# main.net
KiCad netlist of a schematic drawn in EAGLE
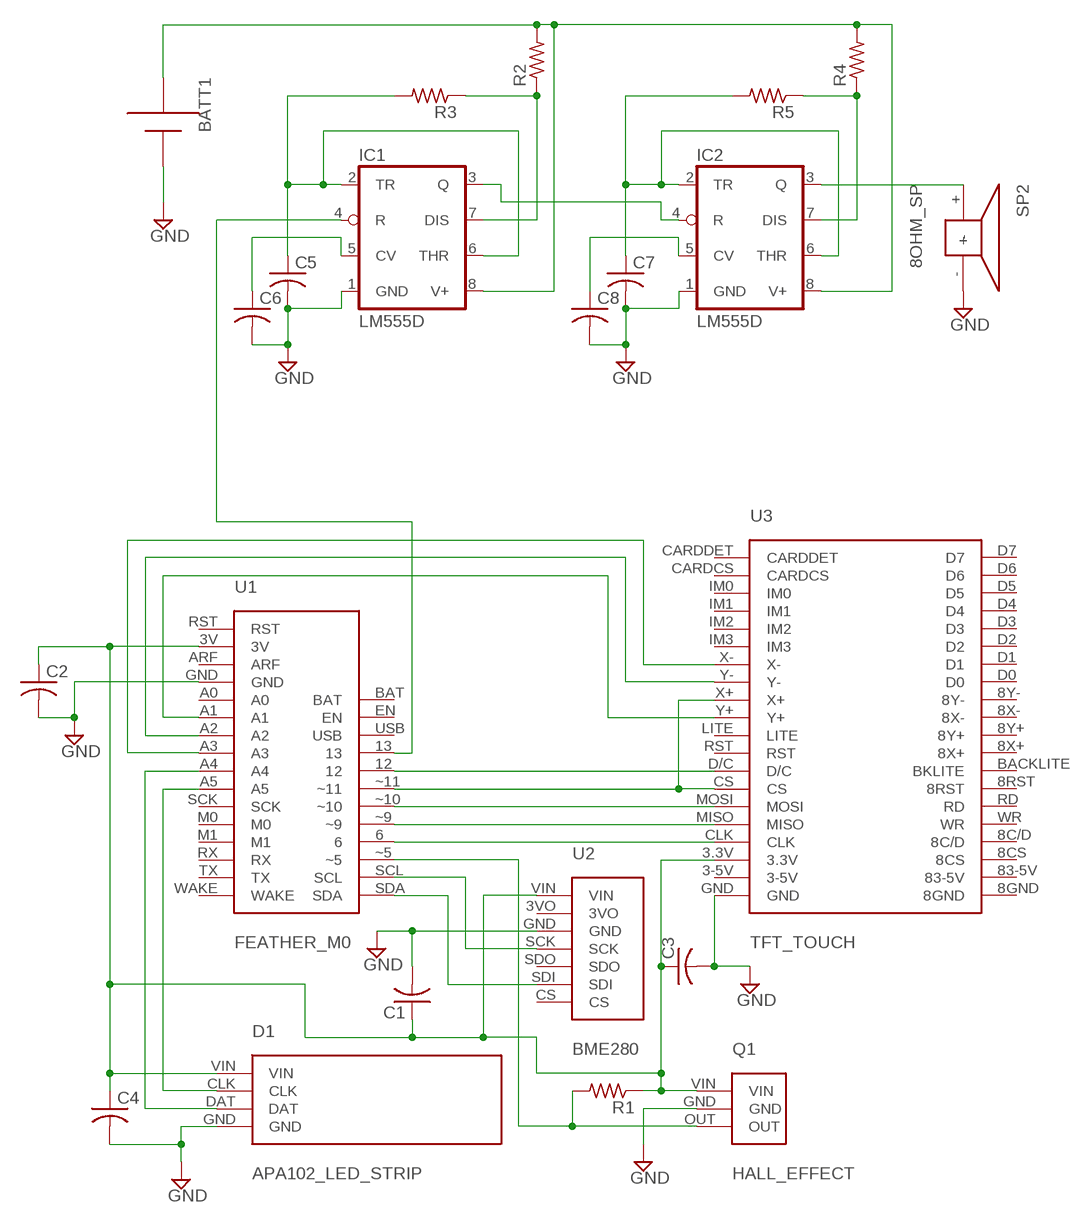
[diagram p0: schematic, sheet 1]

(export (version "E")
  (design (tool "Eeschema 10.0.6"))
  (components
    (comp (ref "BATT1")
      (value "AAA")
      (footprint "eagle-import:12BH412")
      (libsource (lib "eagle-import") (part "AAA"))
    )
    (comp (ref "C1")
      (value "C-US025-024X044")
      (footprint "eagle-import:C025-024X044")
      (libsource (lib "eagle-import") (part "C-US025-024X044"))
    )
    (comp (ref "C2")
      (value "C-US025-024X044")
      (footprint "eagle-import:C025-024X044")
      (libsource (lib "eagle-import") (part "C-US025-024X044"))
    )
    (comp (ref "C3")
      (value "C-US025-024X044")
      (footprint "eagle-import:C025-024X044")
      (libsource (lib "eagle-import") (part "C-US025-024X044"))
    )
    (comp (ref "C4")
      (value "C-US025-024X044")
      (footprint "eagle-import:C025-024X044")
      (libsource (lib "eagle-import") (part "C-US025-024X044"))
    )
    (comp (ref "C5")
      (value "C-US025-024X044")
      (footprint "eagle-import:C025-024X044")
      (libsource (lib "eagle-import") (part "C-US025-024X044"))
    )
    (comp (ref "C6")
      (value "C-US025-024X044")
      (footprint "eagle-import:C025-024X044")
      (libsource (lib "eagle-import") (part "C-US025-024X044"))
    )
    (comp (ref "C7")
      (value "C-US025-024X044")
      (footprint "eagle-import:C025-024X044")
      (libsource (lib "eagle-import") (part "C-US025-024X044"))
    )
    (comp (ref "C8")
      (value "C-US025-024X044")
      (footprint "eagle-import:C025-024X044")
      (libsource (lib "eagle-import") (part "C-US025-024X044"))
    )
    (comp (ref "D1")
      (value "APA102_LED_STRIP")
      (footprint "eagle-import:APA102_LED_STRIP")
      (libsource (lib "eagle-import") (part "APA102_LED_STRIP"))
    )
    (comp (ref "IC1")
      (value "LM555D")
      (footprint "eagle-import:SO08")
      (libsource (lib "eagle-import") (part "555DLM"))
    )
    (comp (ref "IC2")
      (value "LM555D")
      (footprint "eagle-import:SO08")
      (libsource (lib "eagle-import") (part "555DLM"))
    )
    (comp (ref "Q1")
      (value "HALL_EFFECT")
      (footprint "eagle-import:HALL_EFFECT")
      (libsource (lib "eagle-import") (part "HALL_EFFECT"))
    )
    (comp (ref "R1")
      (value "R-US_0207/5V")
      (footprint "eagle-import:0207_5V")
      (libsource (lib "eagle-import") (part "R-US_0207/5V"))
    )
    (comp (ref "R2")
      (value "R-US_0207/5V")
      (footprint "eagle-import:0207_5V")
      (libsource (lib "eagle-import") (part "R-US_0207/5V"))
    )
    (comp (ref "R3")
      (value "R-US_0207/5V")
      (footprint "eagle-import:0207_5V")
      (libsource (lib "eagle-import") (part "R-US_0207/5V"))
    )
    (comp (ref "R4")
      (value "R-US_0207/5V")
      (footprint "eagle-import:0207_5V")
      (libsource (lib "eagle-import") (part "R-US_0207/5V"))
    )
    (comp (ref "R5")
      (value "R-US_0207/5V")
      (footprint "eagle-import:0207_5V")
      (libsource (lib "eagle-import") (part "R-US_0207/5V"))
    )
    (comp (ref "SP2")
      (value "8OHM_SP")
      (footprint "eagle-import:8OHM_SP")
      (libsource (lib "eagle-import") (part "8OHM_SP"))
    )
    (comp (ref "U1")
      (value "FEATHER_M0")
      (footprint "eagle-import:FEATHER_M0")
      (libsource (lib "eagle-import") (part "FEATHER_M0"))
    )
    (comp (ref "U2")
      (value "BME280")
      (footprint "eagle-import:BME280")
      (libsource (lib "eagle-import") (part "BME280"))
    )
    (comp (ref "U3")
      (value "TFT_TOUCH")
      (footprint "eagle-import:TFT_TOUCH")
      (libsource (lib "eagle-import") (part "TFT_TOUCH"))
    )
  )
  (nets
    (net (code "1") (name "GND") (class "Default")
      (node (ref "BATT1") (pin "+") (pinfunction "+_+") (pintype "bidirectional"))
      (node (ref "C1") (pin "2") (pinfunction "2_2") (pintype "passive"))
      (node (ref "C2") (pin "2") (pinfunction "2_2") (pintype "passive"))
      (node (ref "C3") (pin "2") (pinfunction "2_2") (pintype "passive"))
      (node (ref "C4") (pin "2") (pinfunction "2_2") (pintype "passive"))
      (node (ref "C5") (pin "2") (pinfunction "2_2") (pintype "passive"))
      (node (ref "C6") (pin "2") (pinfunction "2_2") (pintype "passive"))
      (node (ref "C7") (pin "2") (pinfunction "2_2") (pintype "passive"))
      (node (ref "C8") (pin "2") (pinfunction "2_2") (pintype "passive"))
      (node (ref "D1") (pin "GND") (pinfunction "GND_GND") (pintype "bidirectional"))
      (node (ref "IC1") (pin "1") (pinfunction "GND_1") (pintype "power_in"))
      (node (ref "IC2") (pin "1") (pinfunction "GND_1") (pintype "power_in"))
      (node (ref "Q1") (pin "GND") (pinfunction "GND_GND") (pintype "bidirectional"))
      (node (ref "SP2") (pin "-") (pinfunction "-_-") (pintype "bidirectional"))
      (node (ref "U1") (pin "GND") (pinfunction "GND_GND") (pintype "bidirectional"))
      (node (ref "U2") (pin "GND") (pinfunction "GND_GND") (pintype "bidirectional"))
      (node (ref "U3") (pin "GND") (pinfunction "GND_GND") (pintype "bidirectional"))
    )
    (net (code "2") (name "Net-(C1-Pad1)") (class "Default")
      (node (ref "C1") (pin "1") (pinfunction "1_1") (pintype "passive"))
      (node (ref "C2") (pin "1") (pinfunction "1_1") (pintype "passive"))
      (node (ref "C3") (pin "1") (pinfunction "1_1") (pintype "passive"))
      (node (ref "C4") (pin "1") (pinfunction "1_1") (pintype "passive"))
      (node (ref "D1") (pin "VIN") (pinfunction "VIN_VIN") (pintype "bidirectional"))
      (node (ref "Q1") (pin "VIN") (pinfunction "VIN_VIN") (pintype "bidirectional"))
      (node (ref "R1") (pin "1") (pinfunction "1_1") (pintype "passive"))
      (node (ref "U1") (pin "3V") (pinfunction "3V_3V") (pintype "bidirectional"))
      (node (ref "U2") (pin "VIN") (pinfunction "VIN_VIN") (pintype "bidirectional"))
      (node (ref "U3") (pin "3.3V") (pinfunction "3.3V_3.3V") (pintype "bidirectional"))
    )
    (net (code "3") (name "Net-(D1-PadCLK)") (class "Default")
      (node (ref "D1") (pin "CLK") (pinfunction "CLK_CLK") (pintype "bidirectional"))
      (node (ref "U1") (pin "A5") (pinfunction "A5_A5") (pintype "bidirectional"))
    )
    (net (code "4") (name "Net-(D1-PadDAT)") (class "Default")
      (node (ref "D1") (pin "DAT") (pinfunction "DAT_DAT") (pintype "bidirectional"))
      (node (ref "U1") (pin "A4") (pinfunction "A4_A4") (pintype "bidirectional"))
    )
    (net (code "5") (name "Net-(IC1-CV)") (class "Default")
      (node (ref "C6") (pin "1") (pinfunction "1_1") (pintype "passive"))
      (node (ref "IC1") (pin "5") (pinfunction "CV_5") (pintype "input"))
    )
    (net (code "6") (name "Net-(IC1-DIS)") (class "Default")
      (node (ref "IC1") (pin "7") (pinfunction "DIS_7") (pintype "input"))
      (node (ref "R2") (pin "1") (pinfunction "1_1") (pintype "passive"))
      (node (ref "R3") (pin "1") (pinfunction "1_1") (pintype "passive"))
    )
    (net (code "7") (name "Net-(IC1-Q)") (class "Default")
      (node (ref "IC1") (pin "3") (pinfunction "Q_3") (pintype "output"))
      (node (ref "IC2") (pin "4") (pinfunction "R_4") (pintype "input"))
    )
    (net (code "8") (name "Net-(IC1-R)") (class "Default")
      (node (ref "IC1") (pin "4") (pinfunction "R_4") (pintype "input"))
      (node (ref "U1") (pin "13") (pinfunction "13_13") (pintype "bidirectional"))
    )
    (net (code "9") (name "Net-(IC1-THR)") (class "Default")
      (node (ref "C5") (pin "1") (pinfunction "1_1") (pintype "passive"))
      (node (ref "IC1") (pin "2") (pinfunction "TR_2") (pintype "input"))
      (node (ref "IC1") (pin "6") (pinfunction "THR_6") (pintype "input"))
      (node (ref "R3") (pin "2") (pinfunction "2_2") (pintype "passive"))
    )
    (net (code "10") (name "Net-(IC1-V+)") (class "Default")
      (node (ref "BATT1") (pin "-") (pinfunction "-_-") (pintype "bidirectional"))
      (node (ref "IC1") (pin "8") (pinfunction "V+_8") (pintype "power_in"))
      (node (ref "IC2") (pin "8") (pinfunction "V+_8") (pintype "power_in"))
      (node (ref "R2") (pin "2") (pinfunction "2_2") (pintype "passive"))
      (node (ref "R4") (pin "2") (pinfunction "2_2") (pintype "passive"))
    )
    (net (code "11") (name "Net-(IC2-CV)") (class "Default")
      (node (ref "C8") (pin "1") (pinfunction "1_1") (pintype "passive"))
      (node (ref "IC2") (pin "5") (pinfunction "CV_5") (pintype "input"))
    )
    (net (code "12") (name "Net-(IC2-DIS)") (class "Default")
      (node (ref "IC2") (pin "7") (pinfunction "DIS_7") (pintype "input"))
      (node (ref "R4") (pin "1") (pinfunction "1_1") (pintype "passive"))
      (node (ref "R5") (pin "1") (pinfunction "1_1") (pintype "passive"))
    )
    (net (code "13") (name "Net-(IC2-Q)") (class "Default")
      (node (ref "IC2") (pin "3") (pinfunction "Q_3") (pintype "output"))
      (node (ref "SP2") (pin "+") (pinfunction "+_+") (pintype "bidirectional"))
    )
    (net (code "14") (name "Net-(IC2-THR)") (class "Default")
      (node (ref "C7") (pin "1") (pinfunction "1_1") (pintype "passive"))
      (node (ref "IC2") (pin "2") (pinfunction "TR_2") (pintype "input"))
      (node (ref "IC2") (pin "6") (pinfunction "THR_6") (pintype "input"))
      (node (ref "R5") (pin "2") (pinfunction "2_2") (pintype "passive"))
    )
    (net (code "15") (name "Net-(U1-Pad6)") (class "Default")
      (node (ref "U1") (pin "6") (pinfunction "6_6") (pintype "bidirectional"))
      (node (ref "U3") (pin "CLK") (pinfunction "CLK_CLK") (pintype "bidirectional"))
    )
    (net (code "16") (name "Net-(U1-Pad12)") (class "Default")
      (node (ref "U1") (pin "12") (pinfunction "12_12") (pintype "bidirectional"))
      (node (ref "U3") (pin "D/C") (pinfunction "D/C_D/C") (pintype "bidirectional"))
    )
    (net (code "17") (name "Net-(U1-PadA1)") (class "Default")
      (node (ref "U1") (pin "A1") (pinfunction "A1_A1") (pintype "bidirectional"))
      (node (ref "U3") (pin "Y+") (pinfunction "Y+_Y+") (pintype "bidirectional"))
    )
    (net (code "18") (name "Net-(U1-PadA2)") (class "Default")
      (node (ref "U1") (pin "A2") (pinfunction "A2_A2") (pintype "bidirectional"))
      (node (ref "U3") (pin "Y-") (pinfunction "Y-_Y-") (pintype "bidirectional"))
    )
    (net (code "19") (name "Net-(U1-PadA3)") (class "Default")
      (node (ref "U1") (pin "A3") (pinfunction "A3_A3") (pintype "bidirectional"))
      (node (ref "U3") (pin "X-") (pinfunction "X-_X-") (pintype "bidirectional"))
    )
    (net (code "20") (name "Net-(U1-PadSCL)") (class "Default")
      (node (ref "U1") (pin "SCL") (pinfunction "SCL_SCL") (pintype "bidirectional"))
      (node (ref "U2") (pin "SCK") (pinfunction "SCK_SCK") (pintype "bidirectional"))
    )
    (net (code "21") (name "Net-(U1-PadSDA)") (class "Default")
      (node (ref "U1") (pin "SDA") (pinfunction "SDA_SDA") (pintype "bidirectional"))
      (node (ref "U2") (pin "SDI") (pinfunction "SDI_SDI") (pintype "bidirectional"))
    )
    (net (code "22") (name "Net-(U1-~{5})") (class "Default")
      (node (ref "Q1") (pin "OUT") (pinfunction "OUT_OUT") (pintype "bidirectional"))
      (node (ref "R1") (pin "2") (pinfunction "2_2") (pintype "passive"))
      (node (ref "U1") (pin "~5") (pinfunction "~{5}_~5") (pintype "bidirectional"))
    )
    (net (code "23") (name "Net-(U1-~{9})") (class "Default")
      (node (ref "U1") (pin "~9") (pinfunction "~{9}_~9") (pintype "bidirectional"))
      (node (ref "U3") (pin "MISO") (pinfunction "MISO_MISO") (pintype "bidirectional"))
    )
    (net (code "24") (name "Net-(U1-~{10})") (class "Default")
      (node (ref "U1") (pin "~10") (pinfunction "~{10}_~10") (pintype "bidirectional"))
      (node (ref "U3") (pin "MOSI") (pinfunction "MOSI_MOSI") (pintype "bidirectional"))
    )
    (net (code "25") (name "Net-(U1-~{11})") (class "Default")
      (node (ref "U1") (pin "~11") (pinfunction "~{11}_~11") (pintype "bidirectional"))
      (node (ref "U3") (pin "CS") (pinfunction "CS_CS") (pintype "bidirectional"))
      (node (ref "U3") (pin "X+") (pinfunction "X+_X+") (pintype "bidirectional"))
    )
    (net (code "26") (name "unconnected-(U1-PadA0)") (class "Default")
      (node (ref "U1") (pin "A0") (pinfunction "A0_A0") (pintype "bidirectional"))
    )
    (net (code "27") (name "unconnected-(U1-PadARF)") (class "Default")
      (node (ref "U1") (pin "ARF") (pinfunction "ARF_ARF") (pintype "bidirectional"))
    )
    (net (code "28") (name "unconnected-(U1-PadBAT)") (class "Default")
      (node (ref "U1") (pin "BAT") (pinfunction "BAT_BAT") (pintype "bidirectional"))
    )
    (net (code "29") (name "unconnected-(U1-PadEN)") (class "Default")
      (node (ref "U1") (pin "EN") (pinfunction "EN_EN") (pintype "bidirectional"))
    )
    (net (code "30") (name "unconnected-(U1-PadM0)") (class "Default")
      (node (ref "U1") (pin "M0") (pinfunction "M0_M0") (pintype "bidirectional"))
    )
    (net (code "31") (name "unconnected-(U1-PadM1)") (class "Default")
      (node (ref "U1") (pin "M1") (pinfunction "M1_M1") (pintype "bidirectional"))
    )
    (net (code "32") (name "unconnected-(U1-PadRST)") (class "Default")
      (node (ref "U1") (pin "RST") (pinfunction "RST_RST") (pintype "bidirectional"))
    )
    (net (code "33") (name "unconnected-(U1-PadRX)") (class "Default")
      (node (ref "U1") (pin "RX") (pinfunction "RX_RX") (pintype "bidirectional"))
    )
    (net (code "34") (name "unconnected-(U1-PadSCK)") (class "Default")
      (node (ref "U1") (pin "SCK") (pinfunction "SCK_SCK") (pintype "bidirectional"))
    )
    (net (code "35") (name "unconnected-(U1-PadTX)") (class "Default")
      (node (ref "U1") (pin "TX") (pinfunction "TX_TX") (pintype "bidirectional"))
    )
    (net (code "36") (name "unconnected-(U1-PadUSB)") (class "Default")
      (node (ref "U1") (pin "USB") (pinfunction "USB_USB") (pintype "bidirectional"))
    )
    (net (code "37") (name "unconnected-(U1-PadWAKE)") (class "Default")
      (node (ref "U1") (pin "WAKE") (pinfunction "WAKE_WAKE") (pintype "bidirectional"))
    )
    (net (code "38") (name "unconnected-(U2-Pad3VO)") (class "Default")
      (node (ref "U2") (pin "3VO") (pinfunction "3VO_3VO") (pintype "bidirectional"))
    )
    (net (code "39") (name "unconnected-(U2-PadCS)") (class "Default")
      (node (ref "U2") (pin "CS") (pinfunction "CS_CS") (pintype "bidirectional"))
    )
    (net (code "40") (name "unconnected-(U2-PadSDO)") (class "Default")
      (node (ref "U2") (pin "SDO") (pinfunction "SDO_SDO") (pintype "bidirectional"))
    )
    (net (code "41") (name "unconnected-(U3-BKLITE-PadBACKLITE)") (class "Default")
      (node (ref "U3") (pin "BACKLITE") (pinfunction "BKLITE_BACKLITE") (pintype "bidirectional"))
    )
    (net (code "42") (name "unconnected-(U3-Pad3-5V)") (class "Default")
      (node (ref "U3") (pin "3-5V") (pinfunction "3-5V_3-5V") (pintype "bidirectional"))
    )
    (net (code "43") (name "unconnected-(U3-Pad8CS)") (class "Default")
      (node (ref "U3") (pin "8CS") (pinfunction "8CS_8CS") (pintype "bidirectional"))
    )
    (net (code "44") (name "unconnected-(U3-Pad8C{slash}D)") (class "Default")
      (node (ref "U3") (pin "8C/D") (pinfunction "8C/D_8C/D") (pintype "bidirectional"))
    )
    (net (code "45") (name "unconnected-(U3-Pad8GND)") (class "Default")
      (node (ref "U3") (pin "8GND") (pinfunction "8GND_8GND") (pintype "bidirectional"))
    )
    (net (code "46") (name "unconnected-(U3-Pad8RST)") (class "Default")
      (node (ref "U3") (pin "8RST") (pinfunction "8RST_8RST") (pintype "bidirectional"))
    )
    (net (code "47") (name "unconnected-(U3-Pad8X+)") (class "Default")
      (node (ref "U3") (pin "8X+") (pinfunction "8X+_8X+") (pintype "bidirectional"))
    )
    (net (code "48") (name "unconnected-(U3-Pad8X-)") (class "Default")
      (node (ref "U3") (pin "8X-") (pinfunction "8X-_8X-") (pintype "bidirectional"))
    )
    (net (code "49") (name "unconnected-(U3-Pad8Y+)") (class "Default")
      (node (ref "U3") (pin "8Y+") (pinfunction "8Y+_8Y+") (pintype "bidirectional"))
    )
    (net (code "50") (name "unconnected-(U3-Pad8Y-)") (class "Default")
      (node (ref "U3") (pin "8Y-") (pinfunction "8Y-_8Y-") (pintype "bidirectional"))
    )
    (net (code "51") (name "unconnected-(U3-Pad83-5V)") (class "Default")
      (node (ref "U3") (pin "83-5V") (pinfunction "83-5V_83-5V") (pintype "bidirectional"))
    )
    (net (code "52") (name "unconnected-(U3-PadCARDCS)") (class "Default")
      (node (ref "U3") (pin "CARDCS") (pinfunction "CARDCS_CARDCS") (pintype "bidirectional"))
    )
    (net (code "53") (name "unconnected-(U3-PadCARDDET)") (class "Default")
      (node (ref "U3") (pin "CARDDET") (pinfunction "CARDDET_CARDDET") (pintype "bidirectional"))
    )
    (net (code "54") (name "unconnected-(U3-PadD0)") (class "Default")
      (node (ref "U3") (pin "D0") (pinfunction "D0_D0") (pintype "bidirectional"))
    )
    (net (code "55") (name "unconnected-(U3-PadD1)") (class "Default")
      (node (ref "U3") (pin "D1") (pinfunction "D1_D1") (pintype "bidirectional"))
    )
    (net (code "56") (name "unconnected-(U3-PadD2)") (class "Default")
      (node (ref "U3") (pin "D2") (pinfunction "D2_D2") (pintype "bidirectional"))
    )
    (net (code "57") (name "unconnected-(U3-PadD3)") (class "Default")
      (node (ref "U3") (pin "D3") (pinfunction "D3_D3") (pintype "bidirectional"))
    )
    (net (code "58") (name "unconnected-(U3-PadD4)") (class "Default")
      (node (ref "U3") (pin "D4") (pinfunction "D4_D4") (pintype "bidirectional"))
    )
    (net (code "59") (name "unconnected-(U3-PadD5)") (class "Default")
      (node (ref "U3") (pin "D5") (pinfunction "D5_D5") (pintype "bidirectional"))
    )
    (net (code "60") (name "unconnected-(U3-PadD6)") (class "Default")
      (node (ref "U3") (pin "D6") (pinfunction "D6_D6") (pintype "bidirectional"))
    )
    (net (code "61") (name "unconnected-(U3-PadD7)") (class "Default")
      (node (ref "U3") (pin "D7") (pinfunction "D7_D7") (pintype "bidirectional"))
    )
    (net (code "62") (name "unconnected-(U3-PadIM0)") (class "Default")
      (node (ref "U3") (pin "IM0") (pinfunction "IM0_IM0") (pintype "bidirectional"))
    )
    (net (code "63") (name "unconnected-(U3-PadIM1)") (class "Default")
      (node (ref "U3") (pin "IM1") (pinfunction "IM1_IM1") (pintype "bidirectional"))
    )
    (net (code "64") (name "unconnected-(U3-PadIM2)") (class "Default")
      (node (ref "U3") (pin "IM2") (pinfunction "IM2_IM2") (pintype "bidirectional"))
    )
    (net (code "65") (name "unconnected-(U3-PadIM3)") (class "Default")
      (node (ref "U3") (pin "IM3") (pinfunction "IM3_IM3") (pintype "bidirectional"))
    )
    (net (code "66") (name "unconnected-(U3-PadLITE)") (class "Default")
      (node (ref "U3") (pin "LITE") (pinfunction "LITE_LITE") (pintype "bidirectional"))
    )
    (net (code "67") (name "unconnected-(U3-PadRD)") (class "Default")
      (node (ref "U3") (pin "RD") (pinfunction "RD_RD") (pintype "bidirectional"))
    )
    (net (code "68") (name "unconnected-(U3-PadRST)") (class "Default")
      (node (ref "U3") (pin "RST") (pinfunction "RST_RST") (pintype "bidirectional"))
    )
    (net (code "69") (name "unconnected-(U3-PadWR)") (class "Default")
      (node (ref "U3") (pin "WR") (pinfunction "WR_WR") (pintype "bidirectional"))
    )
  )
)
